# Sheet2.net
KiCad netlist of a schematic drawn in Altium Designer
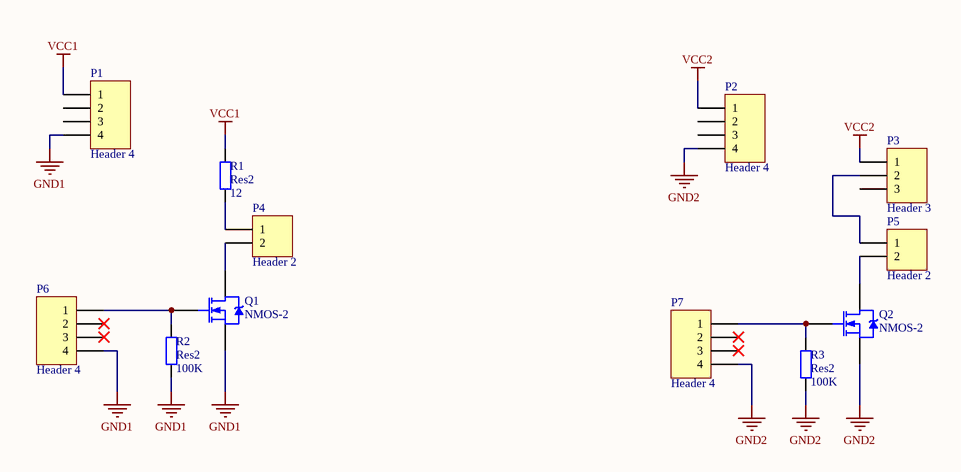
[diagram p0: Sheet2.SchDoc]

(export (version "E")
  (design (tool "Eeschema 10.0.6"))
  (components
    (comp (ref "P1")
      (value "Header 4")
      (footprint "HDR1X4")
      (description "Header, 4-Pin")
      (fields (field (name "PUBLISHER") "Altium Limited"))
      (libsource (lib "Miscellaneous Connectors") (part "Header 4"))
    )
    (comp (ref "P2")
      (value "Header 4")
      (footprint "HDR1X4")
      (description "Header, 4-Pin")
      (fields (field (name "PUBLISHER") "Altium Limited"))
      (libsource (lib "Miscellaneous Connectors") (part "Header 4"))
    )
    (comp (ref "P3")
      (value "Header 3")
      (footprint "HDR1X3")
      (description "Header, 3-Pin")
      (fields (field (name "PUBLISHER") "Altium Limited"))
      (libsource (lib "Miscellaneous Connectors") (part "Header 3"))
    )
    (comp (ref "P4")
      (value "Header 2")
      (footprint "HDR1X2")
      (description "Header, 2-Pin")
      (fields (field (name "PUBLISHER") "Altium Limited"))
      (libsource (lib "Miscellaneous Connectors") (part "Header 2"))
    )
    (comp (ref "P5")
      (value "Header 2")
      (footprint "HDR1X2")
      (description "Header, 2-Pin")
      (fields (field (name "PUBLISHER") "Altium Limited"))
      (libsource (lib "Miscellaneous Connectors") (part "Header 2"))
    )
    (comp (ref "P6")
      (value "Header 4")
      (footprint "HDR1X4")
      (description "Header, 4-Pin")
      (fields (field (name "PUBLISHER") "Altium Limited"))
      (libsource (lib "") (part "Header 4_1"))
    )
    (comp (ref "P7")
      (value "Header 4")
      (footprint "HDR1X4")
      (description "Header, 4-Pin")
      (fields (field (name "PUBLISHER") "Altium Limited"))
      (libsource (lib "") (part "Header 4_1"))
    )
    (comp (ref "Q1")
      (value "NMOS-2")
      (footprint "TO-220AB")
      (description "N-Channel Power MOSFET")
      (fields (field (name "PUBLISHER") "Altium Limited"))
      (libsource (lib "Miscellaneous Devices") (part "NMOS-2"))
    )
    (comp (ref "Q2")
      (value "NMOS-2")
      (footprint "TO-220AB")
      (description "N-Channel Power MOSFET")
      (fields (field (name "PUBLISHER") "Altium Limited"))
      (libsource (lib "Miscellaneous Devices") (part "NMOS-2"))
    )
    (comp (ref "R1")
      (value "Res2")
      (footprint "AXIAL-0.4")
      (description "Resistor")
      (fields (field (name "ALTIUM_VALUE") "12") (field (name "PUBLISHER") "Altium Limited"))
      (libsource (lib "Miscellaneous Devices") (part "Res2"))
    )
    (comp (ref "R2")
      (value "Res2")
      (footprint "AXIAL-0.4")
      (description "Resistor")
      (fields (field (name "ALTIUM_VALUE") "100K") (field (name "PUBLISHER") "Altium Limited"))
      (libsource (lib "Miscellaneous Devices") (part "Res2"))
    )
    (comp (ref "R3")
      (value "Res2")
      (footprint "AXIAL-0.4")
      (description "Resistor")
      (fields (field (name "ALTIUM_VALUE") "100K") (field (name "PUBLISHER") "Altium Limited"))
      (libsource (lib "Miscellaneous Devices") (part "Res2"))
    )
  )
  (nets
    (net (code "1") (name "GND1") (class "Default")
      (node (ref "P1") (pin "4") (pinfunction "4_4") (pintype "passive"))
      (node (ref "P6") (pin "4") (pinfunction "4_4") (pintype "passive"))
      (node (ref "Q1") (pin "3") (pinfunction "S_3") (pintype "passive"))
      (node (ref "R2") (pin "1") (pinfunction "1_1") (pintype "passive"))
    )
    (net (code "2") (name "GND2") (class "Default")
      (node (ref "P2") (pin "4") (pinfunction "4_4") (pintype "passive"))
      (node (ref "P7") (pin "4") (pinfunction "4_4") (pintype "passive"))
      (node (ref "Q2") (pin "3") (pinfunction "S_3") (pintype "passive"))
      (node (ref "R3") (pin "1") (pinfunction "1_1") (pintype "passive"))
    )
    (net (code "3") (name "Net-(P3-Pad2)") (class "Default")
      (node (ref "P3") (pin "2") (pinfunction "2_2") (pintype "passive"))
      (node (ref "P5") (pin "1") (pinfunction "1_1") (pintype "passive"))
    )
    (net (code "4") (name "Net-(P4-Pad1)") (class "Default")
      (node (ref "P4") (pin "1") (pinfunction "1_1") (pintype "passive"))
      (node (ref "R1") (pin "1") (pinfunction "1_1") (pintype "passive"))
    )
    (net (code "5") (name "Net-(Q1-D)") (class "Default")
      (node (ref "P4") (pin "2") (pinfunction "2_2") (pintype "passive"))
      (node (ref "Q1") (pin "2") (pinfunction "D_2") (pintype "passive"))
    )
    (net (code "6") (name "Net-(Q1-G)") (class "Default")
      (node (ref "P6") (pin "1") (pinfunction "1_1") (pintype "passive"))
      (node (ref "Q1") (pin "1") (pinfunction "G_1") (pintype "passive"))
      (node (ref "R2") (pin "2") (pinfunction "2_2") (pintype "passive"))
    )
    (net (code "7") (name "Net-(Q2-D)") (class "Default")
      (node (ref "P5") (pin "2") (pinfunction "2_2") (pintype "passive"))
      (node (ref "Q2") (pin "2") (pinfunction "D_2") (pintype "passive"))
    )
    (net (code "8") (name "Net-(Q2-G)") (class "Default")
      (node (ref "P7") (pin "1") (pinfunction "1_1") (pintype "passive"))
      (node (ref "Q2") (pin "1") (pinfunction "G_1") (pintype "passive"))
      (node (ref "R3") (pin "2") (pinfunction "2_2") (pintype "passive"))
    )
    (net (code "9") (name "VCC1") (class "Default")
      (node (ref "P1") (pin "1") (pinfunction "1_1") (pintype "passive"))
      (node (ref "R1") (pin "2") (pinfunction "2_2") (pintype "passive"))
    )
    (net (code "10") (name "VCC2") (class "Default")
      (node (ref "P2") (pin "1") (pinfunction "1_1") (pintype "passive"))
      (node (ref "P3") (pin "1") (pinfunction "1_1") (pintype "passive"))
    )
    (net (code "11") (name "unconnected-(P1-Pad2)") (class "Default")
      (node (ref "P1") (pin "2") (pinfunction "2_2") (pintype "passive"))
    )
    (net (code "12") (name "unconnected-(P1-Pad3)") (class "Default")
      (node (ref "P1") (pin "3") (pinfunction "3_3") (pintype "passive"))
    )
    (net (code "13") (name "unconnected-(P2-Pad2)") (class "Default")
      (node (ref "P2") (pin "2") (pinfunction "2_2") (pintype "passive"))
    )
    (net (code "14") (name "unconnected-(P2-Pad3)") (class "Default")
      (node (ref "P2") (pin "3") (pinfunction "3_3") (pintype "passive"))
    )
    (net (code "15") (name "unconnected-(P3-Pad3)") (class "Default")
      (node (ref "P3") (pin "3") (pinfunction "3_3") (pintype "passive"))
    )
    (net (code "16") (name "unconnected-(P6-Pad2)") (class "Default")
      (node (ref "P6") (pin "2") (pinfunction "2_2") (pintype "passive+no_connect"))
    )
    (net (code "17") (name "unconnected-(P6-Pad3)") (class "Default")
      (node (ref "P6") (pin "3") (pinfunction "3_3") (pintype "passive+no_connect"))
    )
    (net (code "18") (name "unconnected-(P7-Pad2)") (class "Default")
      (node (ref "P7") (pin "2") (pinfunction "2_2") (pintype "passive+no_connect"))
    )
    (net (code "19") (name "unconnected-(P7-Pad3)") (class "Default")
      (node (ref "P7") (pin "3") (pinfunction "3_3") (pintype "passive+no_connect"))
    )
  )
)
